# GPIOs.net
KiCad netlist of a schematic drawn in Altium Designer
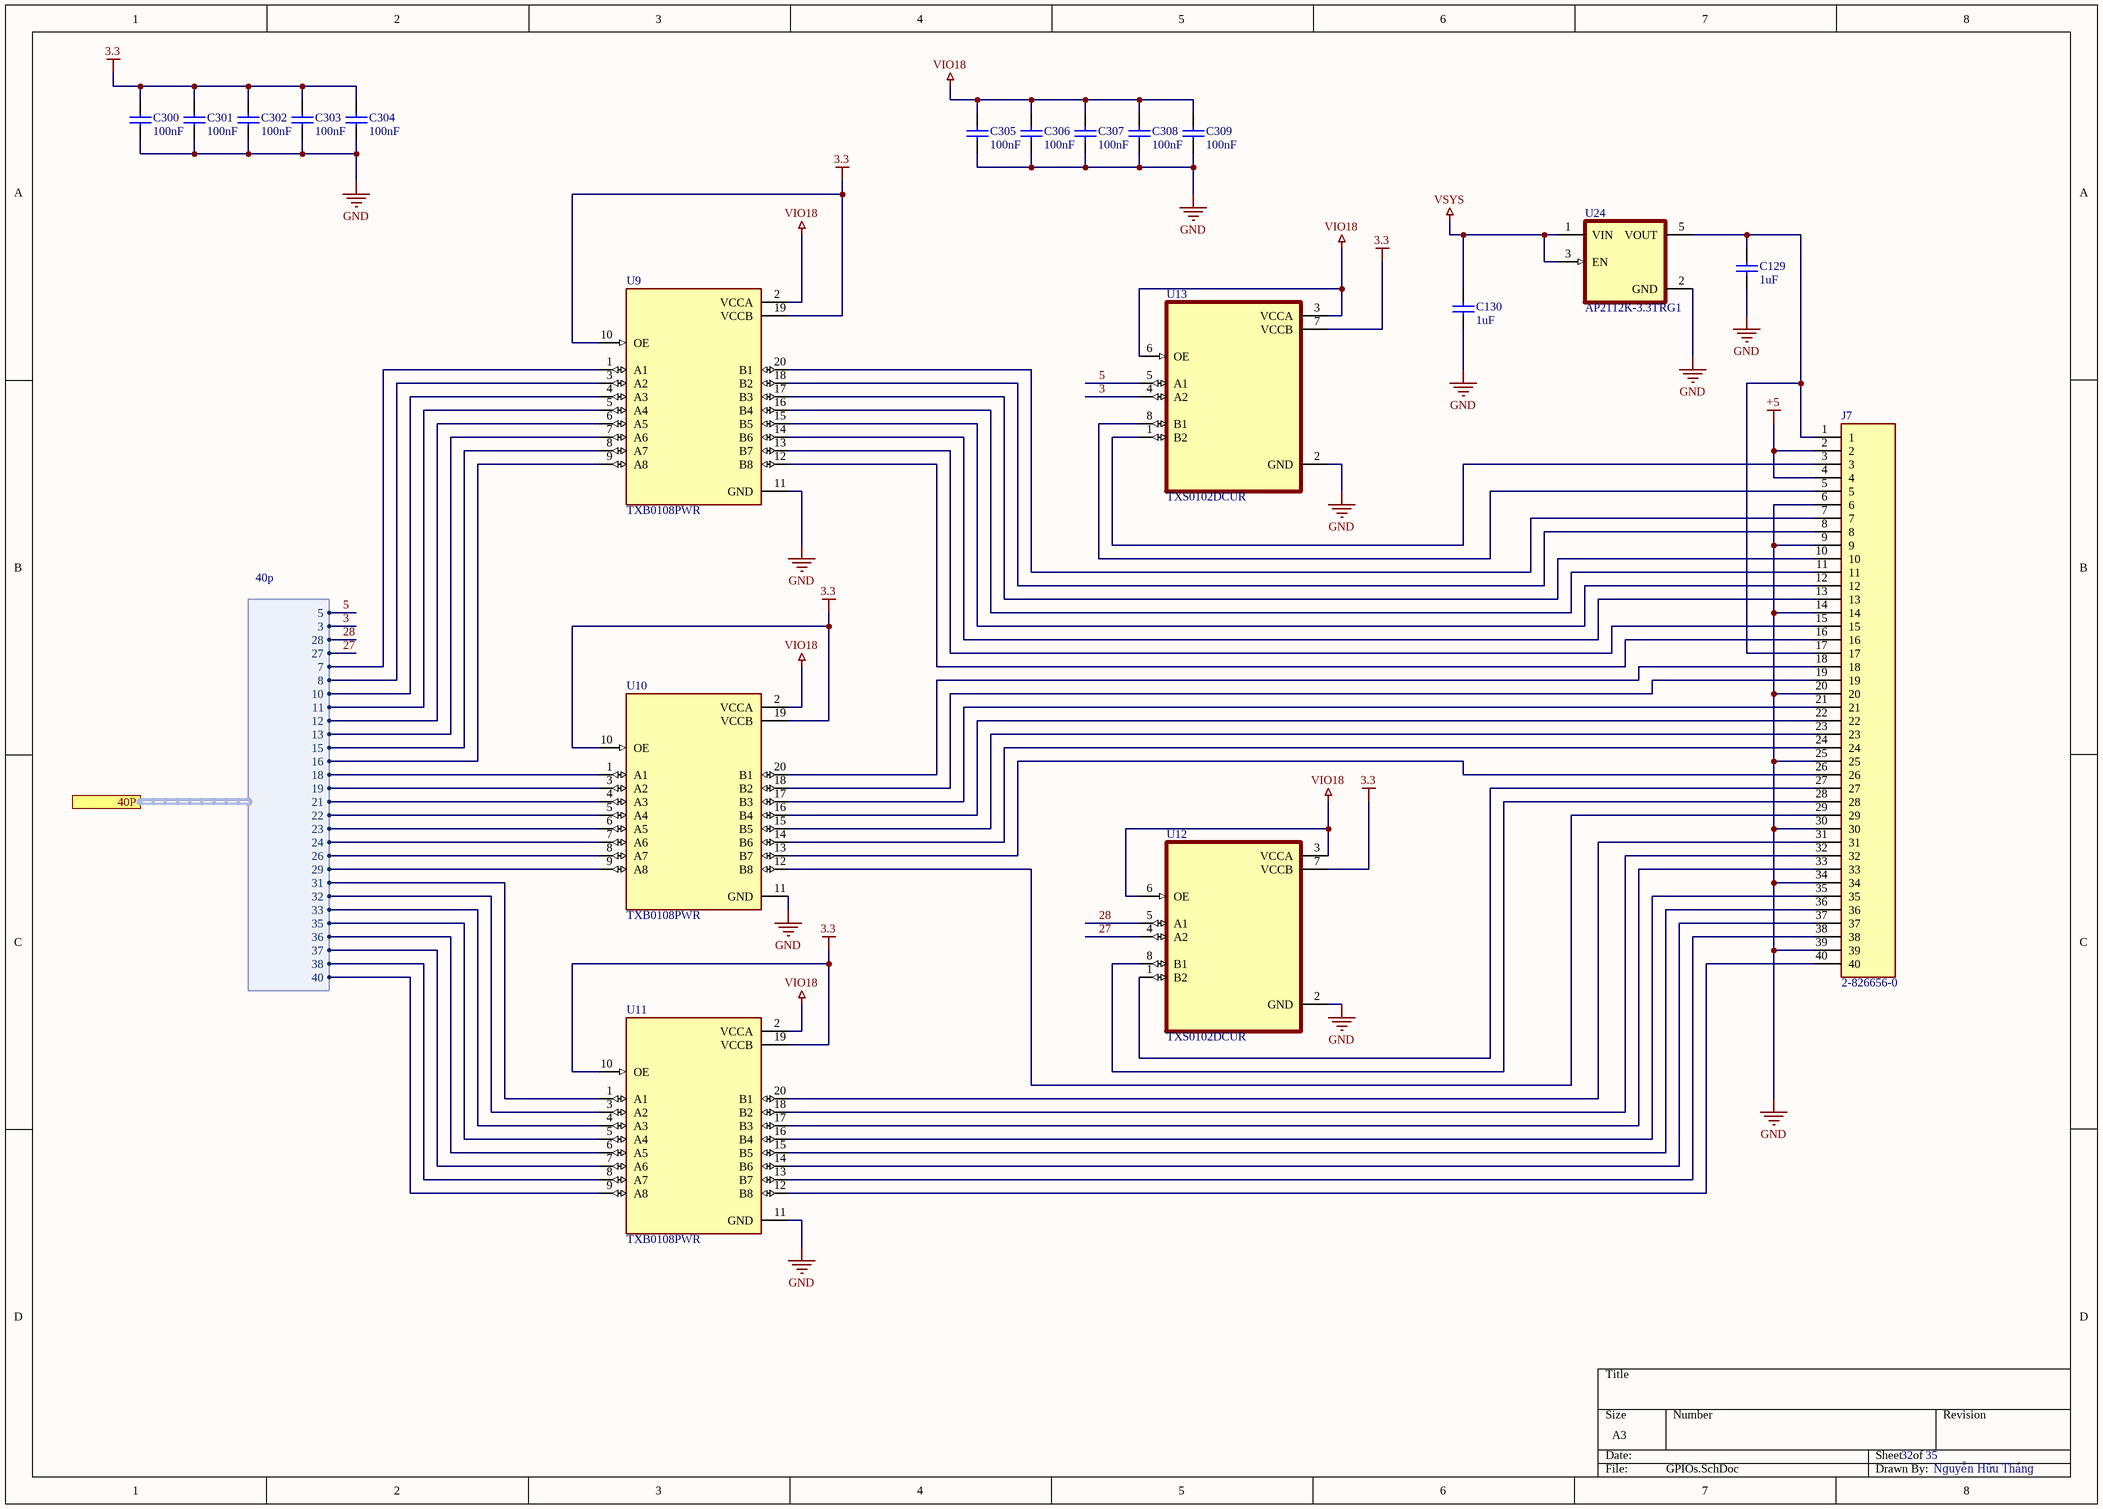
[diagram p0: GPIOs.SchDoc]

(export (version "E")
  (design (tool "Eeschema 10.0.6"))
  (components
    (comp (ref "C129")
      (value "1uF")
      (footprint "C0805")
      (fields (field (name "Comment") "C0805"))
      (libsource (lib "kit") (part "C0805"))
    )
    (comp (ref "C130")
      (value "1uF")
      (footprint "C0805")
      (fields (field (name "Comment") "C0805"))
      (libsource (lib "kit") (part "C0805"))
    )
    (comp (ref "C300")
      (value "100nF")
      (footprint "C0603")
      (fields (field (name "Comment") "C0603"))
      (libsource (lib "kit") (part "C0603"))
    )
    (comp (ref "C301")
      (value "100nF")
      (footprint "C0603")
      (fields (field (name "Comment") "C0603"))
      (libsource (lib "kit") (part "C0603"))
    )
    (comp (ref "C302")
      (value "100nF")
      (footprint "C0603")
      (fields (field (name "Comment") "C0603"))
      (libsource (lib "kit") (part "C0603"))
    )
    (comp (ref "C303")
      (value "100nF")
      (footprint "C0603")
      (fields (field (name "Comment") "C0603"))
      (libsource (lib "kit") (part "C0603"))
    )
    (comp (ref "C304")
      (value "100nF")
      (footprint "C0603")
      (fields (field (name "Comment") "C0603"))
      (libsource (lib "kit") (part "C0603"))
    )
    (comp (ref "C305")
      (value "100nF")
      (footprint "C0603")
      (fields (field (name "Comment") "C0603"))
      (libsource (lib "kit") (part "C0603"))
    )
    (comp (ref "C306")
      (value "100nF")
      (footprint "C0603")
      (fields (field (name "Comment") "C0603"))
      (libsource (lib "kit") (part "C0603"))
    )
    (comp (ref "C307")
      (value "100nF")
      (footprint "C0603")
      (fields (field (name "Comment") "C0603"))
      (libsource (lib "kit") (part "C0603"))
    )
    (comp (ref "C308")
      (value "100nF")
      (footprint "C0603")
      (fields (field (name "Comment") "C0603"))
      (libsource (lib "kit") (part "C0603"))
    )
    (comp (ref "C309")
      (value "100nF")
      (footprint "C0603")
      (fields (field (name "Comment") "C0603"))
      (libsource (lib "kit") (part "C0603"))
    )
    (comp (ref "J7")
      (value "2-826656-0")
      (footprint "TE_2-826656-0")
      (libsource (lib "kit") (part "2-826656-0"))
    )
    (comp (ref "U9")
      (value "TXB0108PWR")
      (footprint "SOP65P640X120-20N")
      (libsource (lib "kit") (part "TXB0108PWR"))
    )
    (comp (ref "U10")
      (value "TXB0108PWR")
      (footprint "SOP65P640X120-20N")
      (libsource (lib "kit") (part "TXB0108PWR"))
    )
    (comp (ref "U11")
      (value "TXB0108PWR")
      (footprint "SOP65P640X120-20N")
      (libsource (lib "kit") (part "TXB0108PWR"))
    )
    (comp (ref "U12")
      (value "TXS0102DCUR")
      (footprint "SOP50P310X90-8N")
      (libsource (lib "kit") (part "TXS0102DCUR"))
    )
    (comp (ref "U13")
      (value "TXS0102DCUR")
      (footprint "SOP50P310X90-8N")
      (libsource (lib "kit") (part "TXS0102DCUR"))
    )
    (comp (ref "U24")
      (value "AP2112K-3.3TRG1")
      (footprint "SOT95P285X140-5N")
      (description "Linear Voltage Regulator IC Positive Fixed 1 Output 600mA SOT-25")
      (libsource (lib "kit") (part "AP2112K-3.3TRG1"))
    )
  )
  (nets
    (net (code "2") (name "+5") (class "Default")
      (node (ref "J7") (pin "2") (pinfunction "2_2") (pintype "passive"))
      (node (ref "J7") (pin "4") (pinfunction "4_4") (pintype "passive"))
    )
    (net (code "3") (name "/3") (class "Default")
      (node (ref "U13") (pin "4") (pinfunction "A2_4") (pintype "bidirectional"))
    )
    (net (code "4") (name "/5") (class "Default")
      (node (ref "U13") (pin "5") (pinfunction "A1_5") (pintype "bidirectional"))
    )
    (net (code "5") (name "/7") (class "Default")
      (node (ref "U9") (pin "1") (pinfunction "A1_1") (pintype "bidirectional"))
    )
    (net (code "6") (name "/8") (class "Default")
      (node (ref "U9") (pin "3") (pinfunction "A2_3") (pintype "bidirectional"))
    )
    (net (code "7") (name "/10") (class "Default")
      (node (ref "U9") (pin "4") (pinfunction "A3_4") (pintype "bidirectional"))
    )
    (net (code "8") (name "/11") (class "Default")
      (node (ref "U9") (pin "5") (pinfunction "A4_5") (pintype "bidirectional"))
    )
    (net (code "9") (name "/12") (class "Default")
      (node (ref "U9") (pin "6") (pinfunction "A5_6") (pintype "bidirectional"))
    )
    (net (code "10") (name "/13") (class "Default")
      (node (ref "U9") (pin "7") (pinfunction "A6_7") (pintype "bidirectional"))
    )
    (net (code "11") (name "/15") (class "Default")
      (node (ref "U9") (pin "8") (pinfunction "A7_8") (pintype "bidirectional"))
    )
    (net (code "12") (name "/16") (class "Default")
      (node (ref "U9") (pin "9") (pinfunction "A8_9") (pintype "bidirectional"))
    )
    (net (code "13") (name "/18") (class "Default")
      (node (ref "U10") (pin "1") (pinfunction "A1_1") (pintype "bidirectional"))
    )
    (net (code "14") (name "/19") (class "Default")
      (node (ref "U10") (pin "3") (pinfunction "A2_3") (pintype "bidirectional"))
    )
    (net (code "15") (name "/21") (class "Default")
      (node (ref "U10") (pin "4") (pinfunction "A3_4") (pintype "bidirectional"))
    )
    (net (code "16") (name "/22") (class "Default")
      (node (ref "U10") (pin "5") (pinfunction "A4_5") (pintype "bidirectional"))
    )
    (net (code "17") (name "/23") (class "Default")
      (node (ref "U10") (pin "6") (pinfunction "A5_6") (pintype "bidirectional"))
    )
    (net (code "18") (name "/24") (class "Default")
      (node (ref "U10") (pin "7") (pinfunction "A6_7") (pintype "bidirectional"))
    )
    (net (code "19") (name "/26") (class "Default")
      (node (ref "U10") (pin "8") (pinfunction "A7_8") (pintype "bidirectional"))
    )
    (net (code "20") (name "/27") (class "Default")
      (node (ref "U12") (pin "4") (pinfunction "A2_4") (pintype "bidirectional"))
    )
    (net (code "21") (name "/28") (class "Default")
      (node (ref "U12") (pin "5") (pinfunction "A1_5") (pintype "bidirectional"))
    )
    (net (code "22") (name "/29") (class "Default")
      (node (ref "U10") (pin "9") (pinfunction "A8_9") (pintype "bidirectional"))
    )
    (net (code "23") (name "/31") (class "Default")
      (node (ref "U11") (pin "1") (pinfunction "A1_1") (pintype "bidirectional"))
    )
    (net (code "24") (name "/32") (class "Default")
      (node (ref "U11") (pin "3") (pinfunction "A2_3") (pintype "bidirectional"))
    )
    (net (code "25") (name "/33") (class "Default")
      (node (ref "U11") (pin "4") (pinfunction "A3_4") (pintype "bidirectional"))
    )
    (net (code "26") (name "/35") (class "Default")
      (node (ref "U11") (pin "5") (pinfunction "A4_5") (pintype "bidirectional"))
    )
    (net (code "27") (name "/36") (class "Default")
      (node (ref "U11") (pin "6") (pinfunction "A5_6") (pintype "bidirectional"))
    )
    (net (code "28") (name "/37") (class "Default")
      (node (ref "U11") (pin "7") (pinfunction "A6_7") (pintype "bidirectional"))
    )
    (net (code "29") (name "/38") (class "Default")
      (node (ref "U11") (pin "8") (pinfunction "A7_8") (pintype "bidirectional"))
    )
    (net (code "30") (name "/40") (class "Default")
      (node (ref "U11") (pin "9") (pinfunction "A8_9") (pintype "bidirectional"))
    )
    (net (code "32") (name "3.3") (class "Default")
      (node (ref "C300") (pin "2") (pinfunction "2_2") (pintype "passive"))
      (node (ref "C301") (pin "2") (pinfunction "2_2") (pintype "passive"))
      (node (ref "C302") (pin "2") (pinfunction "2_2") (pintype "passive"))
      (node (ref "C303") (pin "2") (pinfunction "2_2") (pintype "passive"))
      (node (ref "C304") (pin "2") (pinfunction "2_2") (pintype "passive"))
      (node (ref "U10") (pin "10") (pinfunction "OE_10") (pintype "input"))
      (node (ref "U10") (pin "19") (pinfunction "VCCB_19") (pintype "power_in"))
      (node (ref "U11") (pin "10") (pinfunction "OE_10") (pintype "input"))
      (node (ref "U11") (pin "19") (pinfunction "VCCB_19") (pintype "power_in"))
      (node (ref "U12") (pin "7") (pinfunction "VCCB_7") (pintype "power_in"))
      (node (ref "U13") (pin "7") (pinfunction "VCCB_7") (pintype "power_in"))
      (node (ref "U9") (pin "10") (pinfunction "OE_10") (pintype "input"))
      (node (ref "U9") (pin "19") (pinfunction "VCCB_19") (pintype "power_in"))
    )
    (net (code "33") (name "GND") (class "Default")
      (node (ref "C129") (pin "1") (pinfunction "1_1") (pintype "passive"))
      (node (ref "C130") (pin "1") (pinfunction "1_1") (pintype "passive"))
      (node (ref "C300") (pin "1") (pinfunction "1_1") (pintype "passive"))
      (node (ref "C301") (pin "1") (pinfunction "1_1") (pintype "passive"))
      (node (ref "C302") (pin "1") (pinfunction "1_1") (pintype "passive"))
      (node (ref "C303") (pin "1") (pinfunction "1_1") (pintype "passive"))
      (node (ref "C304") (pin "1") (pinfunction "1_1") (pintype "passive"))
      (node (ref "C305") (pin "1") (pinfunction "1_1") (pintype "passive"))
      (node (ref "C306") (pin "1") (pinfunction "1_1") (pintype "passive"))
      (node (ref "C307") (pin "1") (pinfunction "1_1") (pintype "passive"))
      (node (ref "C308") (pin "1") (pinfunction "1_1") (pintype "passive"))
      (node (ref "C309") (pin "1") (pinfunction "1_1") (pintype "passive"))
      (node (ref "J7") (pin "14") (pinfunction "14_14") (pintype "passive"))
      (node (ref "J7") (pin "20") (pinfunction "20_20") (pintype "passive"))
      (node (ref "J7") (pin "25") (pinfunction "25_25") (pintype "passive"))
      (node (ref "J7") (pin "30") (pinfunction "30_30") (pintype "passive"))
      (node (ref "J7") (pin "34") (pinfunction "34_34") (pintype "passive"))
      (node (ref "J7") (pin "39") (pinfunction "39_39") (pintype "passive"))
      (node (ref "J7") (pin "6") (pinfunction "6_6") (pintype "passive"))
      (node (ref "J7") (pin "9") (pinfunction "9_9") (pintype "passive"))
      (node (ref "U10") (pin "11") (pinfunction "GND_11") (pintype "power_in"))
      (node (ref "U11") (pin "11") (pinfunction "GND_11") (pintype "power_in"))
      (node (ref "U12") (pin "2") (pinfunction "GND_2") (pintype "power_in"))
      (node (ref "U13") (pin "2") (pinfunction "GND_2") (pintype "power_in"))
      (node (ref "U24") (pin "2") (pinfunction "GND_2") (pintype "power_in"))
      (node (ref "U9") (pin "11") (pinfunction "GND_11") (pintype "power_in"))
    )
    (net (code "34") (name "Net-(U9-B1)") (class "Default")
      (node (ref "J7") (pin "7") (pinfunction "7_7") (pintype "passive"))
      (node (ref "U9") (pin "20") (pinfunction "B1_20") (pintype "bidirectional"))
    )
    (net (code "35") (name "Net-(U9-B2)") (class "Default")
      (node (ref "J7") (pin "8") (pinfunction "8_8") (pintype "passive"))
      (node (ref "U9") (pin "18") (pinfunction "B2_18") (pintype "bidirectional"))
    )
    (net (code "36") (name "Net-(U9-B3)") (class "Default")
      (node (ref "J7") (pin "10") (pinfunction "10_10") (pintype "passive"))
      (node (ref "U9") (pin "17") (pinfunction "B3_17") (pintype "bidirectional"))
    )
    (net (code "37") (name "Net-(U9-B4)") (class "Default")
      (node (ref "J7") (pin "11") (pinfunction "11_11") (pintype "passive"))
      (node (ref "U9") (pin "16") (pinfunction "B4_16") (pintype "bidirectional"))
    )
    (net (code "38") (name "Net-(U9-B5)") (class "Default")
      (node (ref "J7") (pin "12") (pinfunction "12_12") (pintype "passive"))
      (node (ref "U9") (pin "15") (pinfunction "B5_15") (pintype "bidirectional"))
    )
    (net (code "39") (name "Net-(U9-B6)") (class "Default")
      (node (ref "J7") (pin "13") (pinfunction "13_13") (pintype "passive"))
      (node (ref "U9") (pin "14") (pinfunction "B6_14") (pintype "bidirectional"))
    )
    (net (code "40") (name "Net-(U9-B7)") (class "Default")
      (node (ref "J7") (pin "15") (pinfunction "15_15") (pintype "passive"))
      (node (ref "U9") (pin "13") (pinfunction "B7_13") (pintype "bidirectional"))
    )
    (net (code "41") (name "Net-(U9-B8)") (class "Default")
      (node (ref "J7") (pin "16") (pinfunction "16_16") (pintype "passive"))
      (node (ref "U9") (pin "12") (pinfunction "B8_12") (pintype "bidirectional"))
    )
    (net (code "42") (name "Net-(U10-B1)") (class "Default")
      (node (ref "J7") (pin "18") (pinfunction "18_18") (pintype "passive"))
      (node (ref "U10") (pin "20") (pinfunction "B1_20") (pintype "bidirectional"))
    )
    (net (code "43") (name "Net-(U10-B2)") (class "Default")
      (node (ref "J7") (pin "19") (pinfunction "19_19") (pintype "passive"))
      (node (ref "U10") (pin "18") (pinfunction "B2_18") (pintype "bidirectional"))
    )
    (net (code "44") (name "Net-(U10-B3)") (class "Default")
      (node (ref "J7") (pin "21") (pinfunction "21_21") (pintype "passive"))
      (node (ref "U10") (pin "17") (pinfunction "B3_17") (pintype "bidirectional"))
    )
    (net (code "45") (name "Net-(U10-B4)") (class "Default")
      (node (ref "J7") (pin "22") (pinfunction "22_22") (pintype "passive"))
      (node (ref "U10") (pin "16") (pinfunction "B4_16") (pintype "bidirectional"))
    )
    (net (code "46") (name "Net-(U10-B5)") (class "Default")
      (node (ref "J7") (pin "23") (pinfunction "23_23") (pintype "passive"))
      (node (ref "U10") (pin "15") (pinfunction "B5_15") (pintype "bidirectional"))
    )
    (net (code "47") (name "Net-(U10-B6)") (class "Default")
      (node (ref "J7") (pin "24") (pinfunction "24_24") (pintype "passive"))
      (node (ref "U10") (pin "14") (pinfunction "B6_14") (pintype "bidirectional"))
    )
    (net (code "48") (name "Net-(U10-B7)") (class "Default")
      (node (ref "J7") (pin "26") (pinfunction "26_26") (pintype "passive"))
      (node (ref "U10") (pin "13") (pinfunction "B7_13") (pintype "bidirectional"))
    )
    (net (code "49") (name "Net-(U10-B8)") (class "Default")
      (node (ref "J7") (pin "29") (pinfunction "29_29") (pintype "passive"))
      (node (ref "U10") (pin "12") (pinfunction "B8_12") (pintype "bidirectional"))
    )
    (net (code "50") (name "Net-(U11-B1)") (class "Default")
      (node (ref "J7") (pin "31") (pinfunction "31_31") (pintype "passive"))
      (node (ref "U11") (pin "20") (pinfunction "B1_20") (pintype "bidirectional"))
    )
    (net (code "51") (name "Net-(U11-B2)") (class "Default")
      (node (ref "J7") (pin "32") (pinfunction "32_32") (pintype "passive"))
      (node (ref "U11") (pin "18") (pinfunction "B2_18") (pintype "bidirectional"))
    )
    (net (code "52") (name "Net-(U11-B3)") (class "Default")
      (node (ref "J7") (pin "33") (pinfunction "33_33") (pintype "passive"))
      (node (ref "U11") (pin "17") (pinfunction "B3_17") (pintype "bidirectional"))
    )
    (net (code "53") (name "Net-(U11-B4)") (class "Default")
      (node (ref "J7") (pin "35") (pinfunction "35_35") (pintype "passive"))
      (node (ref "U11") (pin "16") (pinfunction "B4_16") (pintype "bidirectional"))
    )
    (net (code "54") (name "Net-(U11-B5)") (class "Default")
      (node (ref "J7") (pin "36") (pinfunction "36_36") (pintype "passive"))
      (node (ref "U11") (pin "15") (pinfunction "B5_15") (pintype "bidirectional"))
    )
    (net (code "55") (name "Net-(U11-B6)") (class "Default")
      (node (ref "J7") (pin "37") (pinfunction "37_37") (pintype "passive"))
      (node (ref "U11") (pin "14") (pinfunction "B6_14") (pintype "bidirectional"))
    )
    (net (code "56") (name "Net-(U11-B7)") (class "Default")
      (node (ref "J7") (pin "38") (pinfunction "38_38") (pintype "passive"))
      (node (ref "U11") (pin "13") (pinfunction "B7_13") (pintype "bidirectional"))
    )
    (net (code "57") (name "Net-(U11-B8)") (class "Default")
      (node (ref "J7") (pin "40") (pinfunction "40_40") (pintype "passive"))
      (node (ref "U11") (pin "12") (pinfunction "B8_12") (pintype "bidirectional"))
    )
    (net (code "58") (name "Net-(U12-B1)") (class "Default")
      (node (ref "J7") (pin "28") (pinfunction "28_28") (pintype "passive"))
      (node (ref "U12") (pin "8") (pinfunction "B1_8") (pintype "bidirectional"))
    )
    (net (code "59") (name "Net-(U12-B2)") (class "Default")
      (node (ref "J7") (pin "27") (pinfunction "27_27") (pintype "passive"))
      (node (ref "U12") (pin "1") (pinfunction "B2_1") (pintype "bidirectional"))
    )
    (net (code "60") (name "Net-(U13-B1)") (class "Default")
      (node (ref "J7") (pin "5") (pinfunction "5_5") (pintype "passive"))
      (node (ref "U13") (pin "8") (pinfunction "B1_8") (pintype "bidirectional"))
    )
    (net (code "61") (name "Net-(U13-B2)") (class "Default")
      (node (ref "J7") (pin "3") (pinfunction "3_3") (pintype "passive"))
      (node (ref "U13") (pin "1") (pinfunction "B2_1") (pintype "bidirectional"))
    )
    (net (code "62") (name "Net-(U24-VOUT)") (class "Default")
      (node (ref "C129") (pin "2") (pinfunction "2_2") (pintype "passive"))
      (node (ref "J7") (pin "1") (pinfunction "1_1") (pintype "passive"))
      (node (ref "J7") (pin "17") (pinfunction "17_17") (pintype "passive"))
      (node (ref "U24") (pin "5") (pinfunction "VOUT_5") (pintype "power_in"))
    )
    (net (code "63") (name "VIO18") (class "Default")
      (node (ref "C305") (pin "2") (pinfunction "2_2") (pintype "passive"))
      (node (ref "C306") (pin "2") (pinfunction "2_2") (pintype "passive"))
      (node (ref "C307") (pin "2") (pinfunction "2_2") (pintype "passive"))
      (node (ref "C308") (pin "2") (pinfunction "2_2") (pintype "passive"))
      (node (ref "C309") (pin "2") (pinfunction "2_2") (pintype "passive"))
      (node (ref "U10") (pin "2") (pinfunction "VCCA_2") (pintype "power_in"))
      (node (ref "U11") (pin "2") (pinfunction "VCCA_2") (pintype "power_in"))
      (node (ref "U12") (pin "3") (pinfunction "VCCA_3") (pintype "power_in"))
      (node (ref "U12") (pin "6") (pinfunction "OE_6") (pintype "input"))
      (node (ref "U13") (pin "3") (pinfunction "VCCA_3") (pintype "power_in"))
      (node (ref "U13") (pin "6") (pinfunction "OE_6") (pintype "input"))
      (node (ref "U9") (pin "2") (pinfunction "VCCA_2") (pintype "power_in"))
    )
    (net (code "64") (name "VSYS") (class "Default")
      (node (ref "C130") (pin "2") (pinfunction "2_2") (pintype "passive"))
      (node (ref "U24") (pin "1") (pinfunction "VIN_1") (pintype "power_in"))
      (node (ref "U24") (pin "3") (pinfunction "EN_3") (pintype "input"))
    )
  )
)
